# ir-leds.net
KiCad netlist of a schematic drawn in EAGLE
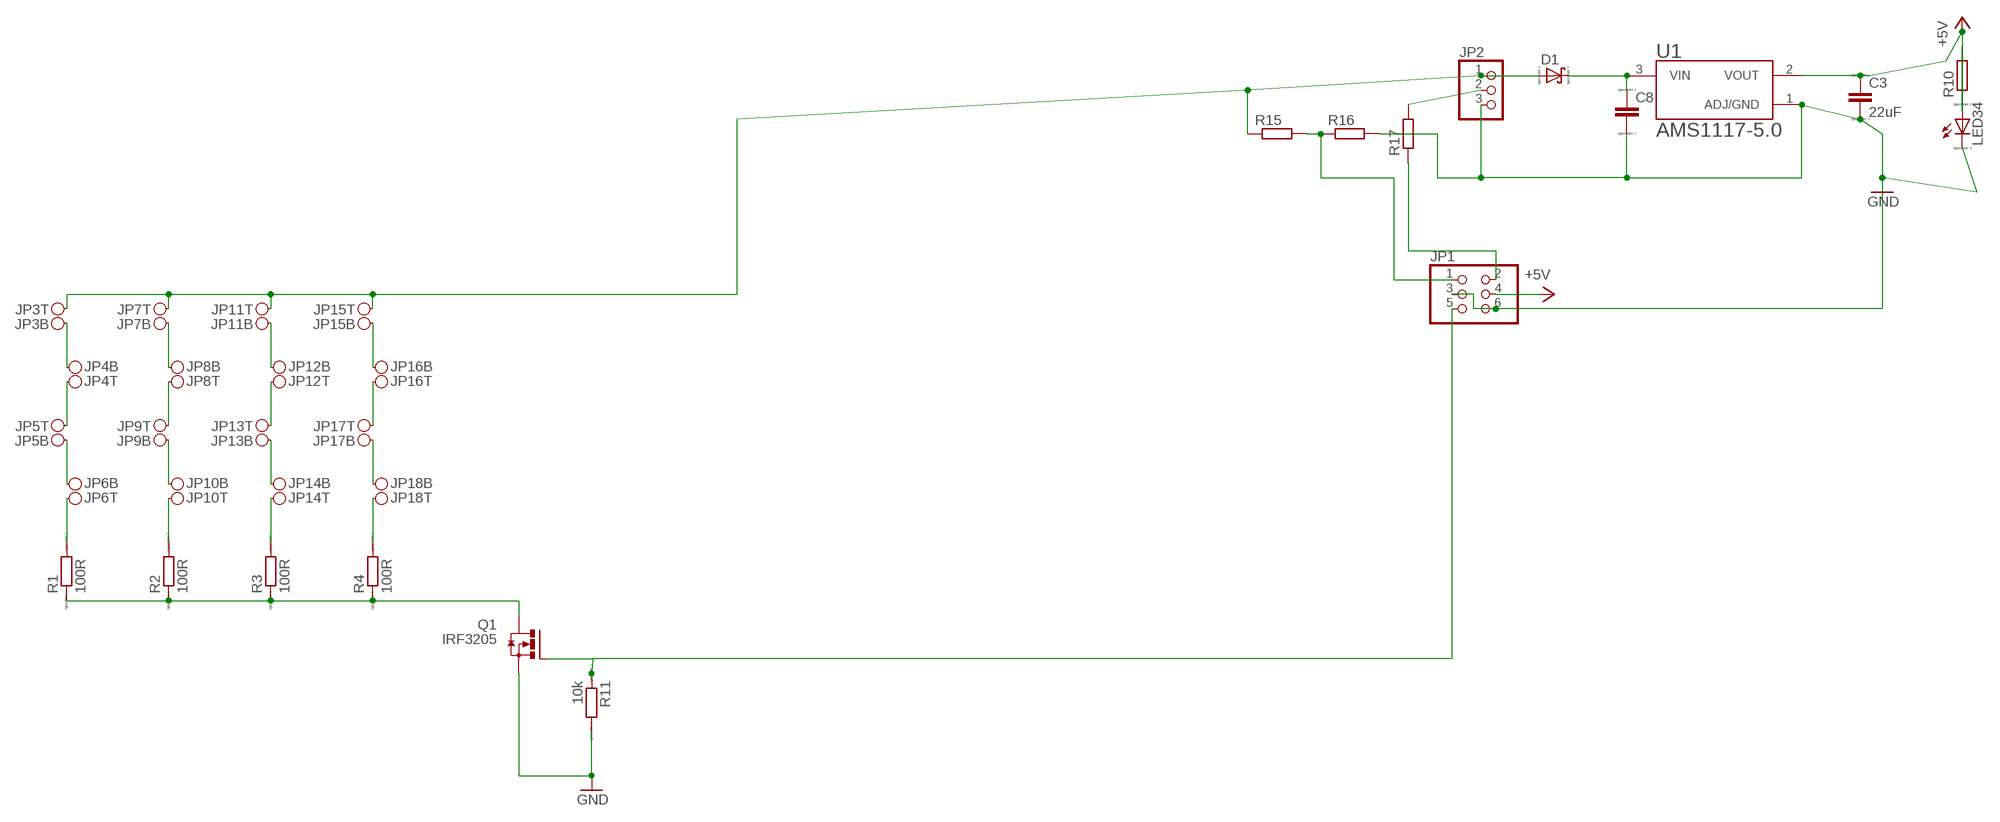
[diagram p0: schematic, sheet 1]

(export (version "E")
  (design (tool "Eeschema 10.0.6"))
  (components
    (comp (ref "C3")
      (value "22uF")
      (footprint "eagle-import:C1206")
      (libsource (lib "eagle-import") (part "CC1206"))
    )
    (comp (ref "C8")
      (value "CC1206")
      (footprint "eagle-import:C1206")
      (libsource (lib "eagle-import") (part "CC1206"))
    )
    (comp (ref "D1")
      (value "SCHOTTKY-DIODEF126Z12")
      (footprint "eagle-import:DIODE_F126Z12")
      (libsource (lib "eagle-import") (part "SCHOTTKY-DIODEF126Z12"))
    )
    (comp (ref "JP1")
      (value "PINHD-2X3")
      (footprint "eagle-import:2X03")
      (libsource (lib "eagle-import") (part "PINHD-2X3"))
    )
    (comp (ref "JP2")
      (value "PINHD-1X3")
      (footprint "eagle-import:1X03")
      (libsource (lib "eagle-import") (part "PINHD-1X3"))
    )
    (comp (ref "JP3")
      (value "PINH2X01")
      (footprint "eagle-import:PINH2X01SMD")
      (libsource (lib "eagle-import") (part "PINH2X01"))
    )
    (comp (ref "JP4")
      (value "PINH2X01")
      (footprint "eagle-import:PINH2X01SMD")
      (libsource (lib "eagle-import") (part "PINH2X01"))
    )
    (comp (ref "JP5")
      (value "PINH2X01")
      (footprint "eagle-import:PINH2X01SMD")
      (libsource (lib "eagle-import") (part "PINH2X01"))
    )
    (comp (ref "JP6")
      (value "PINH2X01")
      (footprint "eagle-import:PINH2X01SMD")
      (libsource (lib "eagle-import") (part "PINH2X01"))
    )
    (comp (ref "JP7")
      (value "PINH2X01")
      (footprint "eagle-import:PINH2X01SMD")
      (libsource (lib "eagle-import") (part "PINH2X01"))
    )
    (comp (ref "JP8")
      (value "PINH2X01")
      (footprint "eagle-import:PINH2X01SMD")
      (libsource (lib "eagle-import") (part "PINH2X01"))
    )
    (comp (ref "JP9")
      (value "PINH2X01")
      (footprint "eagle-import:PINH2X01SMD")
      (libsource (lib "eagle-import") (part "PINH2X01"))
    )
    (comp (ref "JP10")
      (value "PINH2X01")
      (footprint "eagle-import:PINH2X01SMD")
      (libsource (lib "eagle-import") (part "PINH2X01"))
    )
    (comp (ref "JP11")
      (value "PINH2X01")
      (footprint "eagle-import:PINH2X01SMD")
      (libsource (lib "eagle-import") (part "PINH2X01"))
    )
    (comp (ref "JP12")
      (value "PINH2X01")
      (footprint "eagle-import:PINH2X01SMD")
      (libsource (lib "eagle-import") (part "PINH2X01"))
    )
    (comp (ref "JP13")
      (value "PINH2X01")
      (footprint "eagle-import:PINH2X01SMD")
      (libsource (lib "eagle-import") (part "PINH2X01"))
    )
    (comp (ref "JP14")
      (value "PINH2X01")
      (footprint "eagle-import:PINH2X01SMD")
      (libsource (lib "eagle-import") (part "PINH2X01"))
    )
    (comp (ref "JP15")
      (value "PINH2X01")
      (footprint "eagle-import:PINH2X01SMD")
      (libsource (lib "eagle-import") (part "PINH2X01"))
    )
    (comp (ref "JP16")
      (value "PINH2X01")
      (footprint "eagle-import:PINH2X01SMD")
      (libsource (lib "eagle-import") (part "PINH2X01"))
    )
    (comp (ref "JP17")
      (value "PINH2X01")
      (footprint "eagle-import:PINH2X01SMD")
      (libsource (lib "eagle-import") (part "PINH2X01"))
    )
    (comp (ref "JP18")
      (value "PINH2X01")
      (footprint "eagle-import:PINH2X01SMD")
      (libsource (lib "eagle-import") (part "PINH2X01"))
    )
    (comp (ref "LED34")
      (value "LED_E")
      (footprint "eagle-import:LED_1206")
      (libsource (lib "eagle-import") (part "LED_E"))
    )
    (comp (ref "Q1")
      (value "IRF3205")
      (footprint "eagle-import:TO262-V")
      (libsource (lib "eagle-import") (part "IRF3704L-V"))
    )
    (comp (ref "R1")
      (value "100R")
      (footprint "eagle-import:R1206")
      (libsource (lib "eagle-import") (part "RR1206"))
    )
    (comp (ref "R2")
      (value "100R")
      (footprint "eagle-import:R1206")
      (libsource (lib "eagle-import") (part "RR1206"))
    )
    (comp (ref "R3")
      (value "100R")
      (footprint "eagle-import:R1206")
      (libsource (lib "eagle-import") (part "RR1206"))
    )
    (comp (ref "R4")
      (value "100R")
      (footprint "eagle-import:R1206")
      (libsource (lib "eagle-import") (part "RR1206"))
    )
    (comp (ref "R10")
      (value "R-EU_R1206")
      (footprint "eagle-import:R1206")
      (libsource (lib "eagle-import") (part "R-EU_R1206"))
    )
    (comp (ref "R11")
      (value "10k")
      (footprint "eagle-import:R1206")
      (libsource (lib "eagle-import") (part "RR1206"))
    )
    (comp (ref "R15")
      (value "R-EU_R1206")
      (footprint "eagle-import:R1206")
      (libsource (lib "eagle-import") (part "R-EU_R1206"))
    )
    (comp (ref "R16")
      (value "R-EU_R1206")
      (footprint "eagle-import:R1206")
      (libsource (lib "eagle-import") (part "R-EU_R1206"))
    )
    (comp (ref "R17")
      (value "R-EU_R1206")
      (footprint "eagle-import:R1206")
      (libsource (lib "eagle-import") (part "R-EU_R1206"))
    )
    (comp (ref "U1")
      (value "AMS1117-5.0")
      (footprint "eagle-import:SOT229P700X180-4N")
      (fields (field (name "MF") "Advanced Monolithic Systems"))
      (libsource (lib "eagle-import") (part "AMS1117-5.0"))
    )
  )
  (nets
    (net (code "1") (name "+5V") (class "Default")
      (node (ref "C3") (pin "1") (pinfunction "1_1") (pintype "passive"))
      (node (ref "JP1") (pin "4") (pinfunction "4_4") (pintype "passive"))
      (node (ref "R10") (pin "2") (pinfunction "2_2") (pintype "passive"))
      (node (ref "U1") (pin "2") (pinfunction "VOUT_2") (pintype "output"))
    )
    (net (code "2") (name "GND") (class "Default")
      (node (ref "C3") (pin "2") (pinfunction "2_2") (pintype "passive"))
      (node (ref "C8") (pin "2") (pinfunction "2_2") (pintype "passive"))
      (node (ref "JP1") (pin "3") (pinfunction "3_3") (pintype "passive"))
      (node (ref "JP1") (pin "6") (pinfunction "6_6") (pintype "passive"))
      (node (ref "JP2") (pin "3") (pinfunction "3_3") (pintype "passive"))
      (node (ref "LED34") (pin "C") (pinfunction "C_C") (pintype "passive"))
      (node (ref "Q1") (pin "3") (pinfunction "S_3") (pintype "passive"))
      (node (ref "R11") (pin "2") (pinfunction "2_2") (pintype "passive"))
      (node (ref "R16") (pin "2") (pinfunction "2_2") (pintype "passive"))
      (node (ref "U1") (pin "1") (pinfunction "ADJ/GND_1") (pintype "power_in"))
    )
    (net (code "3") (name "Net-(D1-A)") (class "Default")
      (node (ref "C8") (pin "1") (pinfunction "1_1") (pintype "passive"))
      (node (ref "D1") (pin "C") (pinfunction "A_C") (pintype "passive"))
      (node (ref "U1") (pin "3") (pinfunction "VIN_3") (pintype "input"))
    )
    (net (code "4") (name "Net-(D1-C)") (class "Default")
      (node (ref "D1") (pin "A") (pinfunction "C_A") (pintype "passive"))
      (node (ref "JP11") (pin "T1") (pinfunction "1_T1") (pintype "passive"))
      (node (ref "JP15") (pin "T1") (pinfunction "1_T1") (pintype "passive"))
      (node (ref "JP2") (pin "1") (pinfunction "1_1") (pintype "passive"))
      (node (ref "JP3") (pin "T1") (pinfunction "1_T1") (pintype "passive"))
      (node (ref "JP7") (pin "T1") (pinfunction "1_T1") (pintype "passive"))
      (node (ref "R15") (pin "1") (pinfunction "1_1") (pintype "passive"))
    )
    (net (code "5") (name "Net-(JP1-Pad1)") (class "Default")
      (node (ref "JP1") (pin "1") (pinfunction "1_1") (pintype "passive"))
      (node (ref "R15") (pin "2") (pinfunction "2_2") (pintype "passive"))
      (node (ref "R16") (pin "1") (pinfunction "1_1") (pintype "passive"))
    )
    (net (code "6") (name "Net-(JP1-Pad2)") (class "Default")
      (node (ref "JP1") (pin "2") (pinfunction "2_2") (pintype "passive"))
      (node (ref "R17") (pin "1") (pinfunction "1_1") (pintype "passive"))
    )
    (net (code "7") (name "Net-(JP2-Pad2)") (class "Default")
      (node (ref "JP2") (pin "2") (pinfunction "2_2") (pintype "passive"))
      (node (ref "R17") (pin "2") (pinfunction "2_2") (pintype "passive"))
    )
    (net (code "8") (name "Net-(JP3A-1)") (class "Default")
      (node (ref "JP3") (pin "B1") (pinfunction "1_B1") (pintype "passive"))
      (node (ref "JP4") (pin "B1") (pinfunction "1_B1") (pintype "passive"))
    )
    (net (code "9") (name "Net-(JP4B-1)") (class "Default")
      (node (ref "JP4") (pin "T1") (pinfunction "1_T1") (pintype "passive"))
      (node (ref "JP5") (pin "T1") (pinfunction "1_T1") (pintype "passive"))
    )
    (net (code "10") (name "Net-(JP5A-1)") (class "Default")
      (node (ref "JP5") (pin "B1") (pinfunction "1_B1") (pintype "passive"))
      (node (ref "JP6") (pin "B1") (pinfunction "1_B1") (pintype "passive"))
    )
    (net (code "11") (name "Net-(JP6B-1)") (class "Default")
      (node (ref "JP6") (pin "T1") (pinfunction "1_T1") (pintype "passive"))
      (node (ref "R1") (pin "2") (pinfunction "2_2") (pintype "passive"))
    )
    (net (code "12") (name "Net-(JP7A-1)") (class "Default")
      (node (ref "JP7") (pin "B1") (pinfunction "1_B1") (pintype "passive"))
      (node (ref "JP8") (pin "B1") (pinfunction "1_B1") (pintype "passive"))
    )
    (net (code "13") (name "Net-(JP8B-1)") (class "Default")
      (node (ref "JP8") (pin "T1") (pinfunction "1_T1") (pintype "passive"))
      (node (ref "JP9") (pin "T1") (pinfunction "1_T1") (pintype "passive"))
    )
    (net (code "14") (name "Net-(JP10A-1)") (class "Default")
      (node (ref "JP10") (pin "B1") (pinfunction "1_B1") (pintype "passive"))
      (node (ref "JP9") (pin "B1") (pinfunction "1_B1") (pintype "passive"))
    )
    (net (code "15") (name "Net-(JP10B-1)") (class "Default")
      (node (ref "JP10") (pin "T1") (pinfunction "1_T1") (pintype "passive"))
      (node (ref "R2") (pin "2") (pinfunction "2_2") (pintype "passive"))
    )
    (net (code "16") (name "Net-(JP11A-1)") (class "Default")
      (node (ref "JP11") (pin "B1") (pinfunction "1_B1") (pintype "passive"))
      (node (ref "JP12") (pin "B1") (pinfunction "1_B1") (pintype "passive"))
    )
    (net (code "17") (name "Net-(JP12B-1)") (class "Default")
      (node (ref "JP12") (pin "T1") (pinfunction "1_T1") (pintype "passive"))
      (node (ref "JP13") (pin "T1") (pinfunction "1_T1") (pintype "passive"))
    )
    (net (code "18") (name "Net-(JP13A-1)") (class "Default")
      (node (ref "JP13") (pin "B1") (pinfunction "1_B1") (pintype "passive"))
      (node (ref "JP14") (pin "B1") (pinfunction "1_B1") (pintype "passive"))
    )
    (net (code "19") (name "Net-(JP14B-1)") (class "Default")
      (node (ref "JP14") (pin "T1") (pinfunction "1_T1") (pintype "passive"))
      (node (ref "R3") (pin "2") (pinfunction "2_2") (pintype "passive"))
    )
    (net (code "20") (name "Net-(JP15A-1)") (class "Default")
      (node (ref "JP15") (pin "B1") (pinfunction "1_B1") (pintype "passive"))
      (node (ref "JP16") (pin "B1") (pinfunction "1_B1") (pintype "passive"))
    )
    (net (code "21") (name "Net-(JP16B-1)") (class "Default")
      (node (ref "JP16") (pin "T1") (pinfunction "1_T1") (pintype "passive"))
      (node (ref "JP17") (pin "T1") (pinfunction "1_T1") (pintype "passive"))
    )
    (net (code "22") (name "Net-(JP17A-1)") (class "Default")
      (node (ref "JP17") (pin "B1") (pinfunction "1_B1") (pintype "passive"))
      (node (ref "JP18") (pin "B1") (pinfunction "1_B1") (pintype "passive"))
    )
    (net (code "23") (name "Net-(JP18B-1)") (class "Default")
      (node (ref "JP18") (pin "T1") (pinfunction "1_T1") (pintype "passive"))
      (node (ref "R4") (pin "2") (pinfunction "2_2") (pintype "passive"))
    )
    (net (code "24") (name "Net-(LED34-PadA)") (class "Default")
      (node (ref "LED34") (pin "A") (pinfunction "A_A") (pintype "passive"))
      (node (ref "R10") (pin "1") (pinfunction "1_1") (pintype "passive"))
    )
    (net (code "25") (name "Net-(Q1-D)") (class "Default")
      (node (ref "Q1") (pin "2") (pinfunction "D_2") (pintype "passive"))
      (node (ref "R1") (pin "1") (pinfunction "1_1") (pintype "passive"))
      (node (ref "R2") (pin "1") (pinfunction "1_1") (pintype "passive"))
      (node (ref "R3") (pin "1") (pinfunction "1_1") (pintype "passive"))
      (node (ref "R4") (pin "1") (pinfunction "1_1") (pintype "passive"))
    )
    (net (code "26") (name "Net-(Q1-G)") (class "Default")
      (node (ref "JP1") (pin "5") (pinfunction "5_5") (pintype "passive"))
      (node (ref "Q1") (pin "1") (pinfunction "G_1") (pintype "passive"))
      (node (ref "R11") (pin "1") (pinfunction "1_1") (pintype "passive"))
    )
  )
)
